# 05-Front_Panel_SFP.net
KiCad netlist of a schematic drawn in Altium Designer
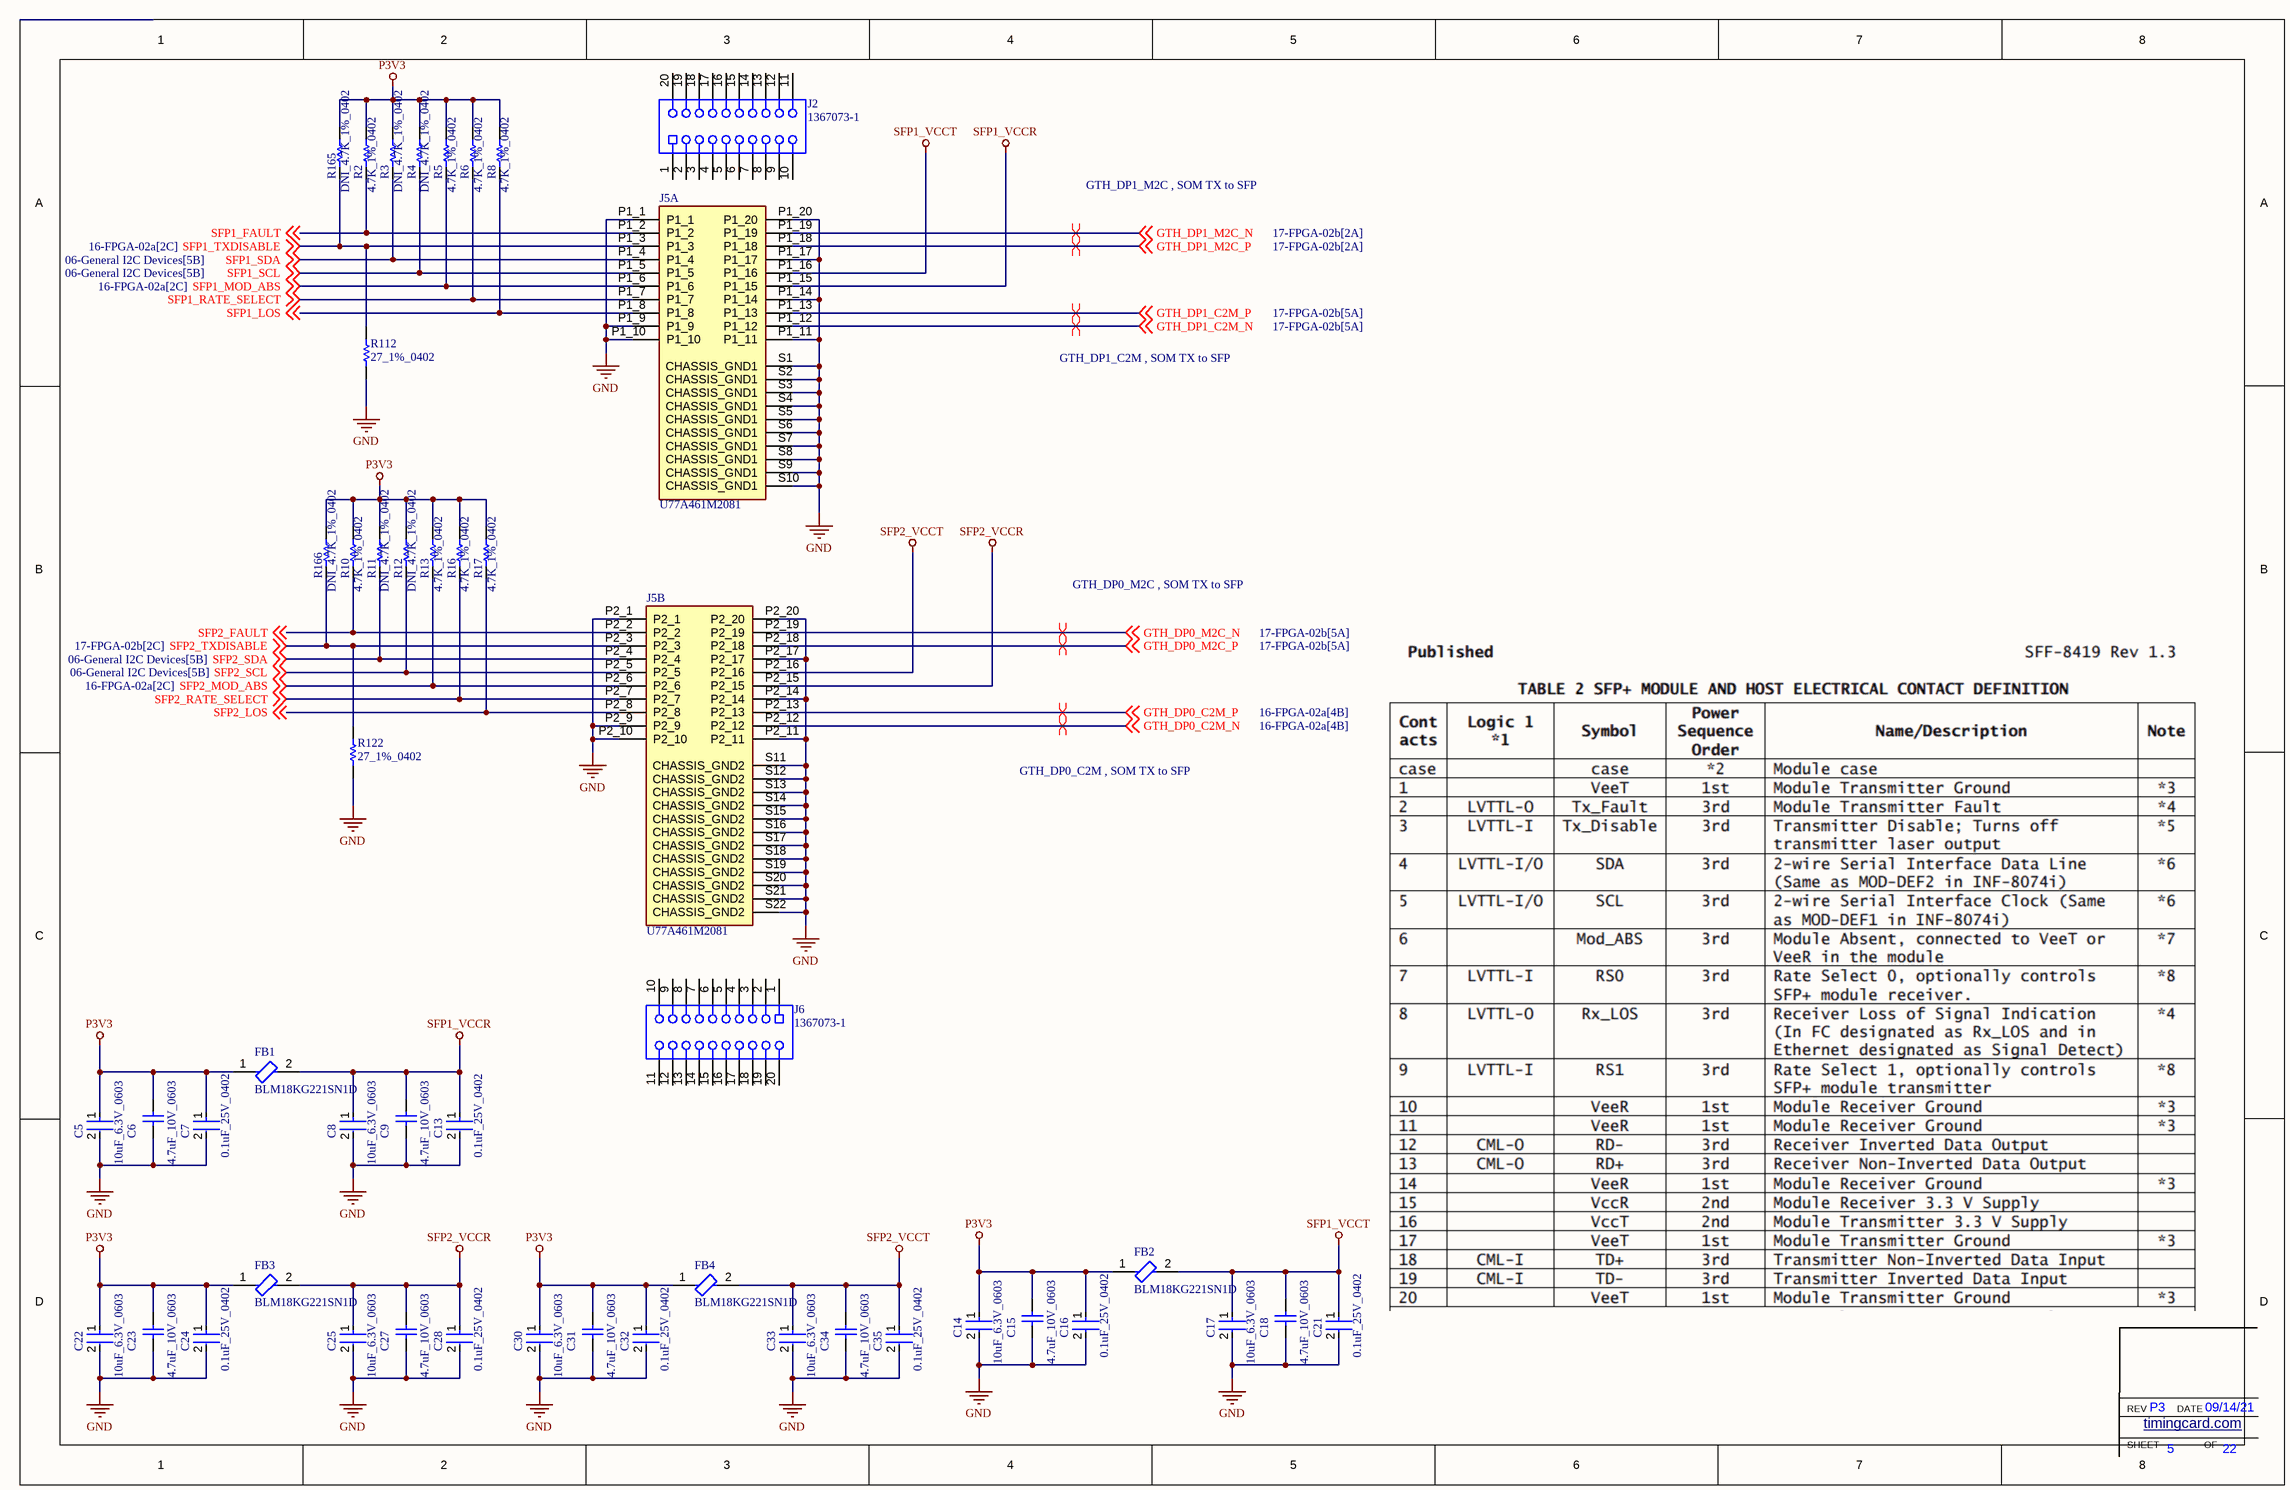
[diagram p0: 05-Front Panel SFP+.SchDoc]

(export (version "E")
  (design (tool "Eeschema 10.0.6"))
  (components
    (comp (ref "C5")
      (value "10uF_6.3V_0603")
      (footprint "FP-C0603C106M9PACTU-MFG")
      (description "CAP CER 10UF 6.3V X5R 0603")
      (fields
        (field (name "MANUFACTURER PART NUMBER") "C0603C106M9PACTU")
        (field (name "MANUFACTURER") "Kemet")
      )
      (libsource (lib "Altium Content Vault") (part "b4654b650e69147ec39a6b967a45e02"))
    )
    (comp (ref "C6")
      (value "4.7uF_10V_0603")
      (footprint "CAPC1608X87X35NL15T15")
      (fields (field (name "PART NUMBER") "C0603C475K8PACTU") (field (name "MANUFACTURER") "Kemet"))
      (libsource (lib "Altium Content Vault") (part "CAP"))
    )
    (comp (ref "C7")
      (value "0.1uF_25V_0402")
      (footprint "FP-0402-L_1_0_1-W_0_5_0_1-IPC_C")
      (description "General Purpose Ceramic Capacitor, 0402, 100nF, 10%, X7R, 15%, 25V")
      (fields (field (name "VOLTAGE") "25V") (field (name "TOLERANCE") "10%"))
      (libsource (lib "Altium Content Vault") (part "b4654b650e69147ec39a6b967a45e02"))
    )
    (comp (ref "C8")
      (value "10uF_6.3V_0603")
      (footprint "FP-C0603C106M9PACTU-MFG")
      (description "CAP CER 10UF 6.3V X5R 0603")
      (fields
        (field (name "MANUFACTURER PART NUMBER") "C0603C106M9PACTU")
        (field (name "MANUFACTURER") "Kemet")
      )
      (libsource (lib "Altium Content Vault") (part "b4654b650e69147ec39a6b967a45e02"))
    )
    (comp (ref "C9")
      (value "4.7uF_10V_0603")
      (footprint "CAPC1608X87X35NL15T15")
      (fields (field (name "PART NUMBER") "C0603C475K8PACTU") (field (name "MANUFACTURER") "Kemet"))
      (libsource (lib "Altium Content Vault") (part "CAP"))
    )
    (comp (ref "C13")
      (value "0.1uF_25V_0402")
      (footprint "FP-0402-L_1_0_1-W_0_5_0_1-IPC_C")
      (description "General Purpose Ceramic Capacitor, 0402, 100nF, 10%, X7R, 15%, 25V")
      (fields (field (name "VOLTAGE") "25V") (field (name "TOLERANCE") "10%"))
      (libsource (lib "Altium Content Vault") (part "b4654b650e69147ec39a6b967a45e02"))
    )
    (comp (ref "C14")
      (value "10uF_6.3V_0603")
      (footprint "FP-C0603C106M9PACTU-MFG")
      (description "CAP CER 10UF 6.3V X5R 0603")
      (fields
        (field (name "MANUFACTURER PART NUMBER") "C0603C106M9PACTU")
        (field (name "MANUFACTURER") "Kemet")
      )
      (libsource (lib "Altium Content Vault") (part "b4654b650e69147ec39a6b967a45e02"))
    )
    (comp (ref "C15")
      (value "4.7uF_10V_0603")
      (footprint "CAPC1608X87X35NL15T15")
      (fields (field (name "PART NUMBER") "C0603C475K8PACTU") (field (name "MANUFACTURER") "Kemet"))
      (libsource (lib "Altium Content Vault") (part "CAP"))
    )
    (comp (ref "C16")
      (value "0.1uF_25V_0402")
      (footprint "FP-0402-L_1_0_1-W_0_5_0_1-IPC_C")
      (description "General Purpose Ceramic Capacitor, 0402, 100nF, 10%, X7R, 15%, 25V")
      (fields (field (name "VOLTAGE") "25V") (field (name "TOLERANCE") "10%"))
      (libsource (lib "Altium Content Vault") (part "b4654b650e69147ec39a6b967a45e02"))
    )
    (comp (ref "C17")
      (value "10uF_6.3V_0603")
      (footprint "FP-C0603C106M9PACTU-MFG")
      (description "CAP CER 10UF 6.3V X5R 0603")
      (fields
        (field (name "MANUFACTURER PART NUMBER") "C0603C106M9PACTU")
        (field (name "MANUFACTURER") "Kemet")
      )
      (libsource (lib "Altium Content Vault") (part "b4654b650e69147ec39a6b967a45e02"))
    )
    (comp (ref "C18")
      (value "4.7uF_10V_0603")
      (footprint "CAPC1608X87X35NL15T15")
      (fields (field (name "PART NUMBER") "C0603C475K8PACTU") (field (name "MANUFACTURER") "Kemet"))
      (libsource (lib "Altium Content Vault") (part "CAP"))
    )
    (comp (ref "C21")
      (value "0.1uF_25V_0402")
      (footprint "FP-0402-L_1_0_1-W_0_5_0_1-IPC_C")
      (description "General Purpose Ceramic Capacitor, 0402, 100nF, 10%, X7R, 15%, 25V")
      (fields (field (name "VOLTAGE") "25V") (field (name "TOLERANCE") "10%"))
      (libsource (lib "Altium Content Vault") (part "b4654b650e69147ec39a6b967a45e02"))
    )
    (comp (ref "C22")
      (value "10uF_6.3V_0603")
      (footprint "FP-C0603C106M9PACTU-MFG")
      (description "CAP CER 10UF 6.3V X5R 0603")
      (fields
        (field (name "MANUFACTURER PART NUMBER") "C0603C106M9PACTU")
        (field (name "MANUFACTURER") "Kemet")
      )
      (libsource (lib "Altium Content Vault") (part "b4654b650e69147ec39a6b967a45e02"))
    )
    (comp (ref "C23")
      (value "4.7uF_10V_0603")
      (footprint "CAPC1608X87X35NL15T15")
      (fields (field (name "PART NUMBER") "C0603C475K8PACTU") (field (name "MANUFACTURER") "Kemet"))
      (libsource (lib "Altium Content Vault") (part "CAP"))
    )
    (comp (ref "C24")
      (value "0.1uF_25V_0402")
      (footprint "FP-0402-L_1_0_1-W_0_5_0_1-IPC_C")
      (description "General Purpose Ceramic Capacitor, 0402, 100nF, 10%, X7R, 15%, 25V")
      (fields (field (name "VOLTAGE") "25V") (field (name "TOLERANCE") "10%"))
      (libsource (lib "Altium Content Vault") (part "b4654b650e69147ec39a6b967a45e02"))
    )
    (comp (ref "C25")
      (value "10uF_6.3V_0603")
      (footprint "FP-C0603C106M9PACTU-MFG")
      (description "CAP CER 10UF 6.3V X5R 0603")
      (fields
        (field (name "MANUFACTURER PART NUMBER") "C0603C106M9PACTU")
        (field (name "MANUFACTURER") "Kemet")
      )
      (libsource (lib "Altium Content Vault") (part "b4654b650e69147ec39a6b967a45e02"))
    )
    (comp (ref "C27")
      (value "4.7uF_10V_0603")
      (footprint "CAPC1608X87X35NL15T15")
      (fields (field (name "PART NUMBER") "C0603C475K8PACTU") (field (name "MANUFACTURER") "Kemet"))
      (libsource (lib "Altium Content Vault") (part "CAP"))
    )
    (comp (ref "C28")
      (value "0.1uF_25V_0402")
      (footprint "FP-0402-L_1_0_1-W_0_5_0_1-IPC_C")
      (description "General Purpose Ceramic Capacitor, 0402, 100nF, 10%, X7R, 15%, 25V")
      (fields (field (name "VOLTAGE") "25V") (field (name "TOLERANCE") "10%"))
      (libsource (lib "Altium Content Vault") (part "b4654b650e69147ec39a6b967a45e02"))
    )
    (comp (ref "C30")
      (value "10uF_6.3V_0603")
      (footprint "FP-C0603C106M9PACTU-MFG")
      (description "CAP CER 10UF 6.3V X5R 0603")
      (fields
        (field (name "MANUFACTURER PART NUMBER") "C0603C106M9PACTU")
        (field (name "MANUFACTURER") "Kemet")
      )
      (libsource (lib "Altium Content Vault") (part "b4654b650e69147ec39a6b967a45e02"))
    )
    (comp (ref "C31")
      (value "4.7uF_10V_0603")
      (footprint "CAPC1608X87X35NL15T15")
      (fields (field (name "PART NUMBER") "C0603C475K8PACTU") (field (name "MANUFACTURER") "Kemet"))
      (libsource (lib "Altium Content Vault") (part "CAP"))
    )
    (comp (ref "C32")
      (value "0.1uF_25V_0402")
      (footprint "FP-0402-L_1_0_1-W_0_5_0_1-IPC_C")
      (description "General Purpose Ceramic Capacitor, 0402, 100nF, 10%, X7R, 15%, 25V")
      (fields (field (name "VOLTAGE") "25V") (field (name "TOLERANCE") "10%"))
      (libsource (lib "Altium Content Vault") (part "b4654b650e69147ec39a6b967a45e02"))
    )
    (comp (ref "C33")
      (value "10uF_6.3V_0603")
      (footprint "FP-C0603C106M9PACTU-MFG")
      (description "CAP CER 10UF 6.3V X5R 0603")
      (fields
        (field (name "MANUFACTURER PART NUMBER") "C0603C106M9PACTU")
        (field (name "MANUFACTURER") "Kemet")
      )
      (libsource (lib "Altium Content Vault") (part "b4654b650e69147ec39a6b967a45e02"))
    )
    (comp (ref "C34")
      (value "4.7uF_10V_0603")
      (footprint "CAPC1608X87X35NL15T15")
      (fields (field (name "PART NUMBER") "C0603C475K8PACTU") (field (name "MANUFACTURER") "Kemet"))
      (libsource (lib "Altium Content Vault") (part "CAP"))
    )
    (comp (ref "C35")
      (value "0.1uF_25V_0402")
      (footprint "FP-0402-L_1_0_1-W_0_5_0_1-IPC_C")
      (description "General Purpose Ceramic Capacitor, 0402, 100nF, 10%, X7R, 15%, 25V")
      (fields (field (name "VOLTAGE") "25V") (field (name "TOLERANCE") "10%"))
      (libsource (lib "Altium Content Vault") (part "b4654b650e69147ec39a6b967a45e02"))
    )
    (comp (ref "FB1")
      (value "BLM18KG221SN1D")
      (footprint "FP-BLM18-0_15-t0_8-IPC_B")
      (description "Chip Ferrite Bead, 0603, 220Ω @ 100MHz, 0.05Ω, 25%, 2.2A")
      (fields (field (name "TOLERANCE") "25%"))
      (libsource (lib "Altium Content Vault") (part "5f30dd21d616792df468990f7003faa"))
    )
    (comp (ref "FB2")
      (value "BLM18KG221SN1D")
      (footprint "FP-BLM18-0_15-t0_8-IPC_B")
      (description "Chip Ferrite Bead, 0603, 220Ω @ 100MHz, 0.05Ω, 25%, 2.2A")
      (fields (field (name "TOLERANCE") "25%"))
      (libsource (lib "Altium Content Vault") (part "5f30dd21d616792df468990f7003faa"))
    )
    (comp (ref "FB3")
      (value "BLM18KG221SN1D")
      (footprint "FP-BLM18-0_15-t0_8-IPC_B")
      (description "Chip Ferrite Bead, 0603, 220Ω @ 100MHz, 0.05Ω, 25%, 2.2A")
      (fields (field (name "TOLERANCE") "25%"))
      (libsource (lib "Altium Content Vault") (part "5f30dd21d616792df468990f7003faa"))
    )
    (comp (ref "FB4")
      (value "BLM18KG221SN1D")
      (footprint "FP-BLM18-0_15-t0_8-IPC_B")
      (description "Chip Ferrite Bead, 0603, 220Ω @ 100MHz, 0.05Ω, 25%, 2.2A")
      (fields (field (name "TOLERANCE") "25%"))
      (libsource (lib "Altium Content Vault") (part "5f30dd21d616792df468990f7003faa"))
    )
    (comp (ref "J2")
      (value "1367073-1")
      (footprint "TECO-1367073-1_V")
      (fields (field (name "MANUFACTURER") "TE Connectivity"))
      (libsource (lib "Altium Content Vault") (part "CN-2P-F-R20_B"))
    )
    (comp (ref "J5")
      (value "U77A461M2081")
      (footprint "AMPHENOL_U77A461M2081")
      (fields (field (name "MF") "AMPHENOL ICC / FCI"))
      (libsource (lib "U77A461M2081") (part "U77A461M2081"))
    )
    (comp (ref "J6")
      (value "1367073-1")
      (footprint "TECO-1367073-1_V")
      (fields (field (name "MANUFACTURER") "TE Connectivity"))
      (libsource (lib "Altium Content Vault") (part "CN-2P-F-R20_B"))
    )
    (comp (ref "R2")
      (value "4.7K_1%_0402")
      (footprint "RESC1005X40X25NL10T10")
      (fields (field (name "MANUFACTURER") "Bourns") (field (name "PART NUMBER") "CR0402-FX-4701GLF"))
      (libsource (lib "Altium Content Vault") (part "RES"))
    )
    (comp (ref "R3")
      (value "DNI_4.7K_1%_0402")
      (footprint "RESC1005X40X25NL10T10")
      (fields (field (name "MANUFACTURER") "Bourns") (field (name "PART NUMBER") "CR0402-FX-4701GLF"))
      (libsource (lib "Altium Content Vault") (part "RES"))
    )
    (comp (ref "R4")
      (value "DNI_4.7K_1%_0402")
      (footprint "RESC1005X40X25NL10T10")
      (fields (field (name "MANUFACTURER") "Bourns") (field (name "PART NUMBER") "CR0402-FX-4701GLF"))
      (libsource (lib "Altium Content Vault") (part "RES"))
    )
    (comp (ref "R5")
      (value "4.7K_1%_0402")
      (footprint "RESC1005X40X25NL10T10")
      (fields (field (name "MANUFACTURER") "Bourns") (field (name "PART NUMBER") "CR0402-FX-4701GLF"))
      (libsource (lib "Altium Content Vault") (part "RES"))
    )
    (comp (ref "R6")
      (value "4.7K_1%_0402")
      (footprint "RESC1005X40X25NL10T10")
      (fields (field (name "MANUFACTURER") "Bourns") (field (name "PART NUMBER") "CR0402-FX-4701GLF"))
      (libsource (lib "Altium Content Vault") (part "RES"))
    )
    (comp (ref "R8")
      (value "4.7K_1%_0402")
      (footprint "RESC1005X40X25NL10T10")
      (fields (field (name "MANUFACTURER") "Bourns") (field (name "PART NUMBER") "CR0402-FX-4701GLF"))
      (libsource (lib "Altium Content Vault") (part "RES"))
    )
    (comp (ref "R10")
      (value "4.7K_1%_0402")
      (footprint "RESC1005X40X25NL10T10")
      (fields (field (name "MANUFACTURER") "Bourns") (field (name "PART NUMBER") "CR0402-FX-4701GLF"))
      (libsource (lib "Altium Content Vault") (part "RES"))
    )
    (comp (ref "R11")
      (value "DNI_4.7K_1%_0402")
      (footprint "RESC1005X40X25NL10T10")
      (fields (field (name "MANUFACTURER") "Bourns") (field (name "PART NUMBER") "CR0402-FX-4701GLF"))
      (libsource (lib "Altium Content Vault") (part "RES"))
    )
    (comp (ref "R12")
      (value "DNI_4.7K_1%_0402")
      (footprint "RESC1005X40X25NL10T10")
      (fields (field (name "MANUFACTURER") "Bourns") (field (name "PART NUMBER") "CR0402-FX-4701GLF"))
      (libsource (lib "Altium Content Vault") (part "RES"))
    )
    (comp (ref "R13")
      (value "4.7K_1%_0402")
      (footprint "RESC1005X40X25NL10T10")
      (fields (field (name "MANUFACTURER") "Bourns") (field (name "PART NUMBER") "CR0402-FX-4701GLF"))
      (libsource (lib "Altium Content Vault") (part "RES"))
    )
    (comp (ref "R16")
      (value "4.7K_1%_0402")
      (footprint "RESC1005X40X25NL10T10")
      (fields (field (name "MANUFACTURER") "Bourns") (field (name "PART NUMBER") "CR0402-FX-4701GLF"))
      (libsource (lib "Altium Content Vault") (part "RES"))
    )
    (comp (ref "R17")
      (value "4.7K_1%_0402")
      (footprint "RESC1005X40X25NL10T10")
      (fields (field (name "MANUFACTURER") "Bourns") (field (name "PART NUMBER") "CR0402-FX-4701GLF"))
      (libsource (lib "Altium Content Vault") (part "RES"))
    )
    (comp (ref "R112")
      (value "27_1%_0402")
      (footprint "RESC1005X40X25NL05T05")
      (fields (field (name "PART NUMBER") "CRCW040227R0FKED") (field (name "MANUFACTURER") "Vishay Dale"))
      (libsource (lib "Altium Content Vault") (part "RES"))
    )
    (comp (ref "R122")
      (value "27_1%_0402")
      (footprint "RESC1005X40X25NL05T05")
      (fields (field (name "PART NUMBER") "CRCW040227R0FKED") (field (name "MANUFACTURER") "Vishay Dale"))
      (libsource (lib "Altium Content Vault") (part "RES"))
    )
    (comp (ref "R165")
      (value "DNI_4.7K_1%_0402")
      (footprint "RESC1005X40X25NL10T10")
      (fields (field (name "MANUFACTURER") "Bourns") (field (name "PART NUMBER") "CR0402-FX-4701GLF"))
      (libsource (lib "Altium Content Vault") (part "RES"))
    )
    (comp (ref "R166")
      (value "DNI_4.7K_1%_0402")
      (footprint "RESC1005X40X25NL10T10")
      (fields (field (name "MANUFACTURER") "Bourns") (field (name "PART NUMBER") "CR0402-FX-4701GLF"))
      (libsource (lib "Altium Content Vault") (part "RES"))
    )
  )
  (nets
    (net (code "1") (name "GND") (class "Default")
      (node (ref "C13") (pin "2") (pinfunction "2_2") (pintype "passive"))
      (node (ref "C14") (pin "2") (pinfunction "2_2") (pintype "passive"))
      (node (ref "C15") (pin "1") (pinfunction "1_1") (pintype "passive"))
      (node (ref "C16") (pin "2") (pinfunction "2_2") (pintype "passive"))
      (node (ref "C17") (pin "2") (pinfunction "2_2") (pintype "passive"))
      (node (ref "C18") (pin "1") (pinfunction "1_1") (pintype "passive"))
      (node (ref "C21") (pin "2") (pinfunction "2_2") (pintype "passive"))
      (node (ref "C22") (pin "2") (pinfunction "2_2") (pintype "passive"))
      (node (ref "C23") (pin "1") (pinfunction "1_1") (pintype "passive"))
      (node (ref "C24") (pin "2") (pinfunction "2_2") (pintype "passive"))
      (node (ref "C25") (pin "2") (pinfunction "2_2") (pintype "passive"))
      (node (ref "C27") (pin "1") (pinfunction "1_1") (pintype "passive"))
      (node (ref "C28") (pin "2") (pinfunction "2_2") (pintype "passive"))
      (node (ref "C30") (pin "2") (pinfunction "2_2") (pintype "passive"))
      (node (ref "C31") (pin "1") (pinfunction "1_1") (pintype "passive"))
      (node (ref "C32") (pin "2") (pinfunction "2_2") (pintype "passive"))
      (node (ref "C33") (pin "2") (pinfunction "2_2") (pintype "passive"))
      (node (ref "C34") (pin "1") (pinfunction "1_1") (pintype "passive"))
      (node (ref "C35") (pin "2") (pinfunction "2_2") (pintype "passive"))
      (node (ref "C5") (pin "2") (pinfunction "2_2") (pintype "passive"))
      (node (ref "C6") (pin "1") (pinfunction "1_1") (pintype "passive"))
      (node (ref "C7") (pin "2") (pinfunction "2_2") (pintype "passive"))
      (node (ref "C8") (pin "2") (pinfunction "2_2") (pintype "passive"))
      (node (ref "C9") (pin "1") (pinfunction "1_1") (pintype "passive"))
      (node (ref "J5") (pin "P1_1") (pinfunction "P1_1_P1_1") (pintype "passive"))
      (node (ref "J5") (pin "P1_10") (pinfunction "P1_10_P1_10") (pintype "passive"))
      (node (ref "J5") (pin "P1_11") (pinfunction "P1_11_P1_11") (pintype "passive"))
      (node (ref "J5") (pin "P1_14") (pinfunction "P1_14_P1_14") (pintype "passive"))
      (node (ref "J5") (pin "P1_17") (pinfunction "P1_17_P1_17") (pintype "passive"))
      (node (ref "J5") (pin "P1_20") (pinfunction "P1_20_P1_20") (pintype "passive"))
      (node (ref "J5") (pin "P1_9") (pinfunction "P1_9_P1_9") (pintype "passive"))
      (node (ref "J5") (pin "P2_1") (pinfunction "P2_1_P2_1") (pintype "passive"))
      (node (ref "J5") (pin "P2_10") (pinfunction "P2_10_P2_10") (pintype "passive"))
      (node (ref "J5") (pin "P2_11") (pinfunction "P2_11_P2_11") (pintype "passive"))
      (node (ref "J5") (pin "P2_14") (pinfunction "P2_14_P2_14") (pintype "passive"))
      (node (ref "J5") (pin "P2_17") (pinfunction "P2_17_P2_17") (pintype "passive"))
      (node (ref "J5") (pin "P2_20") (pinfunction "P2_20_P2_20") (pintype "passive"))
      (node (ref "J5") (pin "P2_9") (pinfunction "P2_9_P2_9") (pintype "passive"))
      (node (ref "J5") (pin "S1") (pinfunction "CHASSIS_GND1_S1") (pintype "power_in"))
      (node (ref "J5") (pin "S10") (pinfunction "CHASSIS_GND1_S10") (pintype "power_in"))
      (node (ref "J5") (pin "S11") (pinfunction "CHASSIS_GND2_S11") (pintype "passive"))
      (node (ref "J5") (pin "S12") (pinfunction "CHASSIS_GND2_S12") (pintype "passive"))
      (node (ref "J5") (pin "S13") (pinfunction "CHASSIS_GND2_S13") (pintype "passive"))
      (node (ref "J5") (pin "S14") (pinfunction "CHASSIS_GND2_S14") (pintype "passive"))
      (node (ref "J5") (pin "S15") (pinfunction "CHASSIS_GND2_S15") (pintype "passive"))
      (node (ref "J5") (pin "S16") (pinfunction "CHASSIS_GND2_S16") (pintype "passive"))
      (node (ref "J5") (pin "S17") (pinfunction "CHASSIS_GND2_S17") (pintype "passive"))
      (node (ref "J5") (pin "S18") (pinfunction "CHASSIS_GND2_S18") (pintype "passive"))
      (node (ref "J5") (pin "S19") (pinfunction "CHASSIS_GND2_S19") (pintype "passive"))
      (node (ref "J5") (pin "S2") (pinfunction "CHASSIS_GND1_S2") (pintype "power_in"))
      (node (ref "J5") (pin "S20") (pinfunction "CHASSIS_GND2_S20") (pintype "passive"))
      (node (ref "J5") (pin "S21") (pinfunction "CHASSIS_GND2_S21") (pintype "passive"))
      (node (ref "J5") (pin "S22") (pinfunction "CHASSIS_GND2_S22") (pintype "passive"))
      (node (ref "J5") (pin "S3") (pinfunction "CHASSIS_GND1_S3") (pintype "power_in"))
      (node (ref "J5") (pin "S4") (pinfunction "CHASSIS_GND1_S4") (pintype "power_in"))
      (node (ref "J5") (pin "S5") (pinfunction "CHASSIS_GND1_S5") (pintype "power_in"))
      (node (ref "J5") (pin "S6") (pinfunction "CHASSIS_GND1_S6") (pintype "power_in"))
      (node (ref "J5") (pin "S7") (pinfunction "CHASSIS_GND1_S7") (pintype "power_in"))
      (node (ref "J5") (pin "S8") (pinfunction "CHASSIS_GND1_S8") (pintype "power_in"))
      (node (ref "J5") (pin "S9") (pinfunction "CHASSIS_GND1_S9") (pintype "power_in"))
      (node (ref "R112") (pin "1") (pinfunction "1_1") (pintype "passive"))
      (node (ref "R122") (pin "1") (pinfunction "1_1") (pintype "passive"))
    )
    (net (code "2") (name "GTH_DP0_C2M_N") (class "Default")
      (node (ref "J5") (pin "P2_12") (pinfunction "P2_12_P2_12") (pintype "passive"))
    )
    (net (code "3") (name "GTH_DP0_C2M_P") (class "Default")
      (node (ref "J5") (pin "P2_13") (pinfunction "P2_13_P2_13") (pintype "passive"))
    )
    (net (code "4") (name "GTH_DP0_M2C_N") (class "Default")
      (node (ref "J5") (pin "P2_19") (pinfunction "P2_19_P2_19") (pintype "passive"))
    )
    (net (code "5") (name "GTH_DP0_M2C_P") (class "Default")
      (node (ref "J5") (pin "P2_18") (pinfunction "P2_18_P2_18") (pintype "passive"))
    )
    (net (code "6") (name "GTH_DP1_C2M_N") (class "Default")
      (node (ref "J5") (pin "P1_12") (pinfunction "P1_12_P1_12") (pintype "passive"))
    )
    (net (code "7") (name "GTH_DP1_C2M_P") (class "Default")
      (node (ref "J5") (pin "P1_13") (pinfunction "P1_13_P1_13") (pintype "passive"))
    )
    (net (code "8") (name "GTH_DP1_M2C_N") (class "Default")
      (node (ref "J5") (pin "P1_19") (pinfunction "P1_19_P1_19") (pintype "passive"))
    )
    (net (code "9") (name "GTH_DP1_M2C_P") (class "Default")
      (node (ref "J5") (pin "P1_18") (pinfunction "P1_18_P1_18") (pintype "passive"))
    )
    (net (code "10") (name "P3V3") (class "Default")
      (node (ref "C14") (pin "1") (pinfunction "1_1") (pintype "passive"))
      (node (ref "C15") (pin "2") (pinfunction "2_2") (pintype "passive"))
      (node (ref "C16") (pin "1") (pinfunction "1_1") (pintype "passive"))
      (node (ref "C22") (pin "1") (pinfunction "1_1") (pintype "passive"))
      (node (ref "C23") (pin "2") (pinfunction "2_2") (pintype "passive"))
      (node (ref "C24") (pin "1") (pinfunction "1_1") (pintype "passive"))
      (node (ref "C30") (pin "1") (pinfunction "1_1") (pintype "passive"))
      (node (ref "C31") (pin "2") (pinfunction "2_2") (pintype "passive"))
      (node (ref "C32") (pin "1") (pinfunction "1_1") (pintype "passive"))
      (node (ref "C5") (pin "1") (pinfunction "1_1") (pintype "passive"))
      (node (ref "C6") (pin "2") (pinfunction "2_2") (pintype "passive"))
      (node (ref "C7") (pin "1") (pinfunction "1_1") (pintype "passive"))
      (node (ref "FB1") (pin "1") (pinfunction "1_1") (pintype "passive"))
      (node (ref "FB2") (pin "1") (pinfunction "1_1") (pintype "passive"))
      (node (ref "FB3") (pin "1") (pinfunction "1_1") (pintype "passive"))
      (node (ref "FB4") (pin "1") (pinfunction "1_1") (pintype "passive"))
      (node (ref "R10") (pin "1") (pinfunction "1_1") (pintype "passive"))
      (node (ref "R11") (pin "1") (pinfunction "1_1") (pintype "passive"))
      (node (ref "R12") (pin "1") (pinfunction "1_1") (pintype "passive"))
      (node (ref "R13") (pin "1") (pinfunction "1_1") (pintype "passive"))
      (node (ref "R16") (pin "1") (pinfunction "1_1") (pintype "passive"))
      (node (ref "R165") (pin "1") (pinfunction "1_1") (pintype "passive"))
      (node (ref "R166") (pin "1") (pinfunction "1_1") (pintype "passive"))
      (node (ref "R17") (pin "1") (pinfunction "1_1") (pintype "passive"))
      (node (ref "R2") (pin "1") (pinfunction "1_1") (pintype "passive"))
      (node (ref "R3") (pin "1") (pinfunction "1_1") (pintype "passive"))
      (node (ref "R4") (pin "1") (pinfunction "1_1") (pintype "passive"))
      (node (ref "R5") (pin "1") (pinfunction "1_1") (pintype "passive"))
      (node (ref "R6") (pin "1") (pinfunction "1_1") (pintype "passive"))
      (node (ref "R8") (pin "1") (pinfunction "1_1") (pintype "passive"))
    )
    (net (code "11") (name "SFP1_FAULT") (class "Default")
      (node (ref "J5") (pin "P1_2") (pinfunction "P1_2_P1_2") (pintype "passive"))
      (node (ref "R2") (pin "2") (pinfunction "2_2") (pintype "passive"))
    )
    (net (code "12") (name "SFP1_LOS") (class "Default")
      (node (ref "J5") (pin "P1_8") (pinfunction "P1_8_P1_8") (pintype "passive"))
      (node (ref "R8") (pin "2") (pinfunction "2_2") (pintype "passive"))
    )
    (net (code "13") (name "SFP1_MOD_ABS") (class "Default")
      (node (ref "J5") (pin "P1_6") (pinfunction "P1_6_P1_6") (pintype "passive"))
      (node (ref "R5") (pin "2") (pinfunction "2_2") (pintype "passive"))
    )
    (net (code "14") (name "SFP1_RATE_SELECT") (class "Default")
      (node (ref "J5") (pin "P1_7") (pinfunction "P1_7_P1_7") (pintype "passive"))
      (node (ref "R6") (pin "2") (pinfunction "2_2") (pintype "passive"))
    )
    (net (code "15") (name "SFP1_SCL") (class "Default")
      (node (ref "J5") (pin "P1_5") (pinfunction "P1_5_P1_5") (pintype "passive"))
      (node (ref "R4") (pin "2") (pinfunction "2_2") (pintype "passive"))
    )
    (net (code "16") (name "SFP1_SDA") (class "Default")
      (node (ref "J5") (pin "P1_4") (pinfunction "P1_4_P1_4") (pintype "passive"))
      (node (ref "R3") (pin "2") (pinfunction "2_2") (pintype "passive"))
    )
    (net (code "17") (name "SFP1_TXDISABLE") (class "Default")
      (node (ref "J5") (pin "P1_3") (pinfunction "P1_3_P1_3") (pintype "passive"))
      (node (ref "R112") (pin "2") (pinfunction "2_2") (pintype "passive"))
      (node (ref "R165") (pin "2") (pinfunction "2_2") (pintype "passive"))
    )
    (net (code "18") (name "SFP1_VCCR") (class "Default")
      (node (ref "C13") (pin "1") (pinfunction "1_1") (pintype "passive"))
      (node (ref "C8") (pin "1") (pinfunction "1_1") (pintype "passive"))
      (node (ref "C9") (pin "2") (pinfunction "2_2") (pintype "passive"))
      (node (ref "FB1") (pin "2") (pinfunction "2_2") (pintype "passive"))
      (node (ref "J5") (pin "P1_15") (pinfunction "P1_15_P1_15") (pintype "passive"))
    )
    (net (code "19") (name "SFP1_VCCT") (class "Default")
      (node (ref "C17") (pin "1") (pinfunction "1_1") (pintype "passive"))
      (node (ref "C18") (pin "2") (pinfunction "2_2") (pintype "passive"))
      (node (ref "C21") (pin "1") (pinfunction "1_1") (pintype "passive"))
      (node (ref "FB2") (pin "2") (pinfunction "2_2") (pintype "passive"))
      (node (ref "J5") (pin "P1_16") (pinfunction "P1_16_P1_16") (pintype "passive"))
    )
    (net (code "20") (name "SFP2_FAULT") (class "Default")
      (node (ref "J5") (pin "P2_2") (pinfunction "P2_2_P2_2") (pintype "passive"))
      (node (ref "R10") (pin "2") (pinfunction "2_2") (pintype "passive"))
    )
    (net (code "21") (name "SFP2_LOS") (class "Default")
      (node (ref "J5") (pin "P2_8") (pinfunction "P2_8_P2_8") (pintype "passive"))
      (node (ref "R17") (pin "2") (pinfunction "2_2") (pintype "passive"))
    )
    (net (code "22") (name "SFP2_MOD_ABS") (class "Default")
      (node (ref "J5") (pin "P2_6") (pinfunction "P2_6_P2_6") (pintype "passive"))
      (node (ref "R13") (pin "2") (pinfunction "2_2") (pintype "passive"))
    )
    (net (code "23") (name "SFP2_RATE_SELECT") (class "Default")
      (node (ref "J5") (pin "P2_7") (pinfunction "P2_7_P2_7") (pintype "passive"))
      (node (ref "R16") (pin "2") (pinfunction "2_2") (pintype "passive"))
    )
    (net (code "24") (name "SFP2_SCL") (class "Default")
      (node (ref "J5") (pin "P2_5") (pinfunction "P2_5_P2_5") (pintype "passive"))
      (node (ref "R12") (pin "2") (pinfunction "2_2") (pintype "passive"))
    )
    (net (code "25") (name "SFP2_SDA") (class "Default")
      (node (ref "J5") (pin "P2_4") (pinfunction "P2_4_P2_4") (pintype "passive"))
      (node (ref "R11") (pin "2") (pinfunction "2_2") (pintype "passive"))
    )
    (net (code "26") (name "SFP2_TXDISABLE") (class "Default")
      (node (ref "J5") (pin "P2_3") (pinfunction "P2_3_P2_3") (pintype "passive"))
      (node (ref "R122") (pin "2") (pinfunction "2_2") (pintype "passive"))
      (node (ref "R166") (pin "2") (pinfunction "2_2") (pintype "passive"))
    )
    (net (code "27") (name "SFP2_VCCR") (class "Default")
      (node (ref "C25") (pin "1") (pinfunction "1_1") (pintype "passive"))
      (node (ref "C27") (pin "2") (pinfunction "2_2") (pintype "passive"))
      (node (ref "C28") (pin "1") (pinfunction "1_1") (pintype "passive"))
      (node (ref "FB3") (pin "2") (pinfunction "2_2") (pintype "passive"))
      (node (ref "J5") (pin "P2_15") (pinfunction "P2_15_P2_15") (pintype "passive"))
    )
    (net (code "28") (name "SFP2_VCCT") (class "Default")
      (node (ref "C33") (pin "1") (pinfunction "1_1") (pintype "passive"))
      (node (ref "C34") (pin "2") (pinfunction "2_2") (pintype "passive"))
      (node (ref "C35") (pin "1") (pinfunction "1_1") (pintype "passive"))
      (node (ref "FB4") (pin "2") (pinfunction "2_2") (pintype "passive"))
      (node (ref "J5") (pin "P2_16") (pinfunction "P2_16_P2_16") (pintype "passive"))
    )
    (net (code "29") (name "unconnected-(J2-Pad1)") (class "Default")
      (node (ref "J2") (pin "1") (pinfunction "1_1") (pintype "passive"))
    )
    (net (code "30") (name "unconnected-(J2-Pad2)") (class "Default")
      (node (ref "J2") (pin "2") (pinfunction "2_2") (pintype "passive"))
    )
    (net (code "31") (name "unconnected-(J2-Pad3)") (class "Default")
      (node (ref "J2") (pin "3") (pinfunction "3_3") (pintype "passive"))
    )
    (net (code "32") (name "unconnected-(J2-Pad4)") (class "Default")
      (node (ref "J2") (pin "4") (pinfunction "4_4") (pintype "passive"))
    )
    (net (code "33") (name "unconnected-(J2-Pad5)") (class "Default")
      (node (ref "J2") (pin "5") (pinfunction "5_5") (pintype "passive"))
    )
    (net (code "34") (name "unconnected-(J2-Pad6)") (class "Default")
      (node (ref "J2") (pin "6") (pinfunction "6_6") (pintype "passive"))
    )
    (net (code "35") (name "unconnected-(J2-Pad7)") (class "Default")
      (node (ref "J2") (pin "7") (pinfunction "7_7") (pintype "passive"))
    )
    (net (code "36") (name "unconnected-(J2-Pad8)") (class "Default")
      (node (ref "J2") (pin "8") (pinfunction "8_8") (pintype "passive"))
    )
    (net (code "37") (name "unconnected-(J2-Pad9)") (class "Default")
      (node (ref "J2") (pin "9") (pinfunction "9_9") (pintype "passive"))
    )
    (net (code "38") (name "unconnected-(J2-Pad10)") (class "Default")
      (node (ref "J2") (pin "10") (pinfunction "10_10") (pintype "passive"))
    )
    (net (code "39") (name "unconnected-(J2-Pad11)") (class "Default")
      (node (ref "J2") (pin "11") (pinfunction "11_11") (pintype "passive"))
    )
    (net (code "40") (name "unconnected-(J2-Pad12)") (class "Default")
      (node (ref "J2") (pin "12") (pinfunction "12_12") (pintype "passive"))
    )
    (net (code "41") (name "unconnected-(J2-Pad13)") (class "Default")
      (node (ref "J2") (pin "13") (pinfunction "13_13") (pintype "passive"))
    )
    (net (code "42") (name "unconnected-(J2-Pad14)") (class "Default")
      (node (ref "J2") (pin "14") (pinfunction "14_14") (pintype "passive"))
    )
    (net (code "43") (name "unconnected-(J2-Pad15)") (class "Default")
      (node (ref "J2") (pin "15") (pinfunction "15_15") (pintype "passive"))
    )
    (net (code "44") (name "unconnected-(J2-Pad16)") (class "Default")
      (node (ref "J2") (pin "16") (pinfunction "16_16") (pintype "passive"))
    )
    (net (code "45") (name "unconnected-(J2-Pad17)") (class "Default")
      (node (ref "J2") (pin "17") (pinfunction "17_17") (pintype "passive"))
    )
    (net (code "46") (name "unconnected-(J2-Pad18)") (class "Default")
      (node (ref "J2") (pin "18") (pinfunction "18_18") (pintype "passive"))
    )
    (net (code "47") (name "unconnected-(J2-Pad19)") (class "Default")
      (node (ref "J2") (pin "19") (pinfunction "19_19") (pintype "passive"))
    )
    (net (code "48") (name "unconnected-(J2-Pad20)") (class "Default")
      (node (ref "J2") (pin "20") (pinfunction "20_20") (pintype "passive"))
    )
    (net (code "49") (name "unconnected-(J6-Pad1)") (class "Default")
      (node (ref "J6") (pin "1") (pinfunction "1_1") (pintype "passive"))
    )
    (net (code "50") (name "unconnected-(J6-Pad2)") (class "Default")
      (node (ref "J6") (pin "2") (pinfunction "2_2") (pintype "passive"))
    )
    (net (code "51") (name "unconnected-(J6-Pad3)") (class "Default")
      (node (ref "J6") (pin "3") (pinfunction "3_3") (pintype "passive"))
    )
    (net (code "52") (name "unconnected-(J6-Pad4)") (class "Default")
      (node (ref "J6") (pin "4") (pinfunction "4_4") (pintype "passive"))
    )
    (net (code "53") (name "unconnected-(J6-Pad5)") (class "Default")
      (node (ref "J6") (pin "5") (pinfunction "5_5") (pintype "passive"))
    )
    (net (code "54") (name "unconnected-(J6-Pad6)") (class "Default")
      (node (ref "J6") (pin "6") (pinfunction "6_6") (pintype "passive"))
    )
    (net (code "55") (name "unconnected-(J6-Pad7)") (class "Default")
      (node (ref "J6") (pin "7") (pinfunction "7_7") (pintype "passive"))
    )
    (net (code "56") (name "unconnected-(J6-Pad8)") (class "Default")
      (node (ref "J6") (pin "8") (pinfunction "8_8") (pintype "passive"))
    )
    (net (code "57") (name "unconnected-(J6-Pad9)") (class "Default")
      (node (ref "J6") (pin "9") (pinfunction "9_9") (pintype "passive"))
    )
    (net (code "58") (name "unconnected-(J6-Pad10)") (class "Default")
      (node (ref "J6") (pin "10") (pinfunction "10_10") (pintype "passive"))
    )
    (net (code "59") (name "unconnected-(J6-Pad11)") (class "Default")
      (node (ref "J6") (pin "11") (pinfunction "11_11") (pintype "passive"))
    )
    (net (code "60") (name "unconnected-(J6-Pad12)") (class "Default")
      (node (ref "J6") (pin "12") (pinfunction "12_12") (pintype "passive"))
    )
    (net (code "61") (name "unconnected-(J6-Pad13)") (class "Default")
      (node (ref "J6") (pin "13") (pinfunction "13_13") (pintype "passive"))
    )
    (net (code "62") (name "unconnected-(J6-Pad14)") (class "Default")
      (node (ref "J6") (pin "14") (pinfunction "14_14") (pintype "passive"))
    )
    (net (code "63") (name "unconnected-(J6-Pad15)") (class "Default")
      (node (ref "J6") (pin "15") (pinfunction "15_15") (pintype "passive"))
    )
    (net (code "64") (name "unconnected-(J6-Pad16)") (class "Default")
      (node (ref "J6") (pin "16") (pinfunction "16_16") (pintype "passive"))
    )
    (net (code "65") (name "unconnected-(J6-Pad17)") (class "Default")
      (node (ref "J6") (pin "17") (pinfunction "17_17") (pintype "passive"))
    )
    (net (code "66") (name "unconnected-(J6-Pad18)") (class "Default")
      (node (ref "J6") (pin "18") (pinfunction "18_18") (pintype "passive"))
    )
    (net (code "67") (name "unconnected-(J6-Pad19)") (class "Default")
      (node (ref "J6") (pin "19") (pinfunction "19_19") (pintype "passive"))
    )
    (net (code "68") (name "unconnected-(J6-Pad20)") (class "Default")
      (node (ref "J6") (pin "20") (pinfunction "20_20") (pintype "passive"))
    )
  )
)
